# usb2serial-pic14f1454s.net
KiCad netlist of a schematic drawn in EAGLE
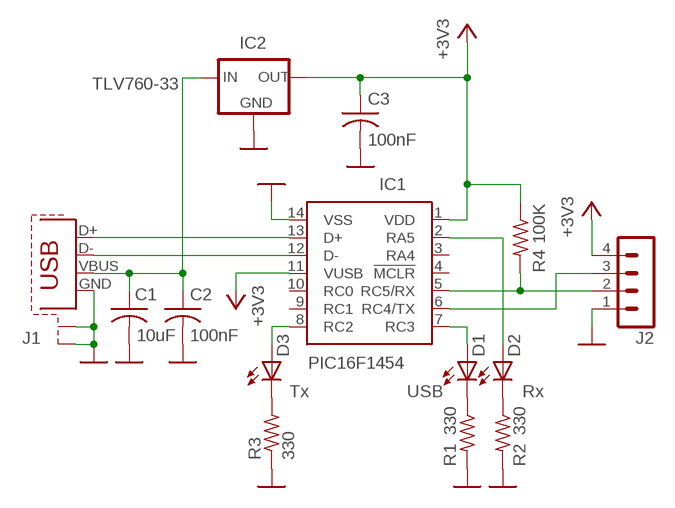
[diagram p0: schematic, sheet 1]

(export (version "E")
  (design (tool "Eeschema 10.0.6"))
  (components
    (comp (ref "C1")
      (value "10uF")
      (footprint "eagle-import:C0805")
      (libsource (lib "eagle-import") (part "C-USC0805"))
    )
    (comp (ref "C2")
      (value "100nF")
      (footprint "eagle-import:C0805")
      (libsource (lib "eagle-import") (part "C-USC0805"))
    )
    (comp (ref "C3")
      (value "100nF")
      (footprint "eagle-import:C0805")
      (libsource (lib "eagle-import") (part "C-USC0805"))
    )
    (comp (ref "D1")
      (value "Green")
      (footprint "eagle-import:CHIPLED_0805")
      (libsource (lib "eagle-import") (part "LEDCHIPLED_0805"))
    )
    (comp (ref "D2")
      (value "Green")
      (footprint "eagle-import:CHIPLED_0805")
      (libsource (lib "eagle-import") (part "LEDCHIPLED_0805"))
    )
    (comp (ref "D3")
      (value "Green")
      (footprint "eagle-import:CHIPLED_0805")
      (libsource (lib "eagle-import") (part "LEDCHIPLED_0805"))
    )
    (comp (ref "IC1")
      (value "PIC16F1454")
      (footprint "eagle-import:SOIC-14")
      (libsource (lib "eagle-import") (part "PIC16F1454-SOIC"))
    )
    (comp (ref "IC2")
      (value "TLV760-33")
      (footprint "eagle-import:SOT23")
      (libsource (lib "eagle-import") (part "TLV760"))
    )
    (comp (ref "J1")
      (value "USB-SHIELD-A-H1")
      (footprint "eagle-import:USB-A-H1")
      (libsource (lib "eagle-import") (part "USB-SHIELD-A-H1"))
    )
    (comp (ref "J2")
      (value "J2")
      (footprint "eagle-import:MA04-1")
      (libsource (lib "eagle-import") (part "MA04-1"))
    )
    (comp (ref "R1")
      (value "330")
      (footprint "eagle-import:R0805")
      (libsource (lib "eagle-import") (part "R-US_R0805"))
    )
    (comp (ref "R2")
      (value "330")
      (footprint "eagle-import:R0805")
      (libsource (lib "eagle-import") (part "R-US_R0805"))
    )
    (comp (ref "R3")
      (value "330")
      (footprint "eagle-import:R0805")
      (libsource (lib "eagle-import") (part "R-US_R0805"))
    )
    (comp (ref "R4")
      (value "100K")
      (footprint "eagle-import:R0805")
      (libsource (lib "eagle-import") (part "R-US_R0805"))
    )
  )
  (nets
    (net (code "1") (name "+3V3") (class "Default")
      (node (ref "C3") (pin "1") (pinfunction "1_1") (pintype "passive"))
      (node (ref "IC1") (pin "1") (pinfunction "VDD_1") (pintype "power_in"))
      (node (ref "IC1") (pin "11") (pinfunction "VUSB_11") (pintype "power_in"))
      (node (ref "IC2") (pin "1") (pinfunction "OUT_1") (pintype "passive"))
      (node (ref "J2") (pin "4") (pinfunction "4_4") (pintype "passive"))
      (node (ref "R4") (pin "1") (pinfunction "1_1") (pintype "passive"))
    )
    (net (code "2") (name "GND") (class "Default")
      (node (ref "C1") (pin "2") (pinfunction "2_2") (pintype "passive"))
      (node (ref "C2") (pin "2") (pinfunction "2_2") (pintype "passive"))
      (node (ref "C3") (pin "2") (pinfunction "2_2") (pintype "passive"))
      (node (ref "IC1") (pin "14") (pinfunction "VSS_14") (pintype "power_in"))
      (node (ref "IC2") (pin "3") (pinfunction "GND_3") (pintype "input"))
      (node (ref "J1") (pin "GND") (pinfunction "GND_GND") (pintype "passive"))
      (node (ref "J1") (pin "GND2") (pinfunction "S1_GND2") (pintype "passive"))
      (node (ref "J1") (pin "GND3") (pinfunction "S2_GND3") (pintype "passive"))
      (node (ref "J2") (pin "1") (pinfunction "1_1") (pintype "passive"))
      (node (ref "R1") (pin "2") (pinfunction "2_2") (pintype "passive"))
      (node (ref "R2") (pin "2") (pinfunction "2_2") (pintype "passive"))
      (node (ref "R3") (pin "1") (pinfunction "1_1") (pintype "passive"))
    )
    (net (code "3") (name "Net-(D1-PadC)") (class "Default")
      (node (ref "D1") (pin "C") (pinfunction "C_C") (pintype "passive"))
      (node (ref "R1") (pin "1") (pinfunction "1_1") (pintype "passive"))
    )
    (net (code "4") (name "Net-(D2-PadC)") (class "Default")
      (node (ref "D2") (pin "C") (pinfunction "C_C") (pintype "passive"))
      (node (ref "R2") (pin "1") (pinfunction "1_1") (pintype "passive"))
    )
    (net (code "5") (name "Net-(D3-PadC)") (class "Default")
      (node (ref "D3") (pin "C") (pinfunction "C_C") (pintype "passive"))
      (node (ref "R3") (pin "2") (pinfunction "2_2") (pintype "passive"))
    )
    (net (code "6") (name "Net-(IC1-D+)") (class "Default")
      (node (ref "IC1") (pin "13") (pinfunction "D+_13") (pintype "passive"))
      (node (ref "J1") (pin "D+") (pinfunction "D+_D+") (pintype "passive"))
    )
    (net (code "7") (name "Net-(IC1-D-)") (class "Default")
      (node (ref "IC1") (pin "12") (pinfunction "D-_12") (pintype "passive"))
      (node (ref "J1") (pin "D-") (pinfunction "D-_D-") (pintype "passive"))
    )
    (net (code "8") (name "Net-(IC1-RA5)") (class "Default")
      (node (ref "D2") (pin "A") (pinfunction "A_A") (pintype "passive"))
      (node (ref "IC1") (pin "2") (pinfunction "RA5_2") (pintype "bidirectional"))
    )
    (net (code "9") (name "Net-(IC1-RC2)") (class "Default")
      (node (ref "D3") (pin "A") (pinfunction "A_A") (pintype "passive"))
      (node (ref "IC1") (pin "8") (pinfunction "RC2_8") (pintype "bidirectional"))
    )
    (net (code "10") (name "Net-(IC1-RC3)") (class "Default")
      (node (ref "D1") (pin "A") (pinfunction "A_A") (pintype "passive"))
      (node (ref "IC1") (pin "7") (pinfunction "RC3_7") (pintype "bidirectional"))
    )
    (net (code "11") (name "Net-(IC1-RC4{slash}TX)") (class "Default")
      (node (ref "IC1") (pin "6") (pinfunction "RC4/TX_6") (pintype "input"))
      (node (ref "J2") (pin "3") (pinfunction "3_3") (pintype "passive"))
    )
    (net (code "12") (name "Net-(IC1-RC5{slash}RX)") (class "Default")
      (node (ref "IC1") (pin "5") (pinfunction "RC5/RX_5") (pintype "bidirectional"))
      (node (ref "J2") (pin "2") (pinfunction "2_2") (pintype "passive"))
      (node (ref "R4") (pin "2") (pinfunction "2_2") (pintype "passive"))
    )
    (net (code "13") (name "Net-(IC2-IN)") (class "Default")
      (node (ref "C1") (pin "1") (pinfunction "1_1") (pintype "passive"))
      (node (ref "C2") (pin "1") (pinfunction "1_1") (pintype "passive"))
      (node (ref "IC2") (pin "2") (pinfunction "IN_2") (pintype "input"))
      (node (ref "J1") (pin "VBUS") (pinfunction "VBUS_VBUS") (pintype "passive"))
    )
    (net (code "14") (name "unconnected-(IC1-RA4-Pad3)") (class "Default")
      (node (ref "IC1") (pin "3") (pinfunction "RA4_3") (pintype "bidirectional"))
    )
    (net (code "15") (name "unconnected-(IC1-RC0-Pad10)") (class "Default")
      (node (ref "IC1") (pin "10") (pinfunction "RC0_10") (pintype "bidirectional"))
    )
    (net (code "16") (name "unconnected-(IC1-RC1-Pad9)") (class "Default")
      (node (ref "IC1") (pin "9") (pinfunction "RC1_9") (pintype "bidirectional"))
    )
    (net (code "17") (name "unconnected-(IC1-~{MCLR}-Pad4)") (class "Default")
      (node (ref "IC1") (pin "4") (pinfunction "~{MCLR}_4") (pintype "bidirectional"))
    )
  )
)
